# DB_Pheripherals-X01.net
KiCad netlist of a schematic drawn in Altium Designer
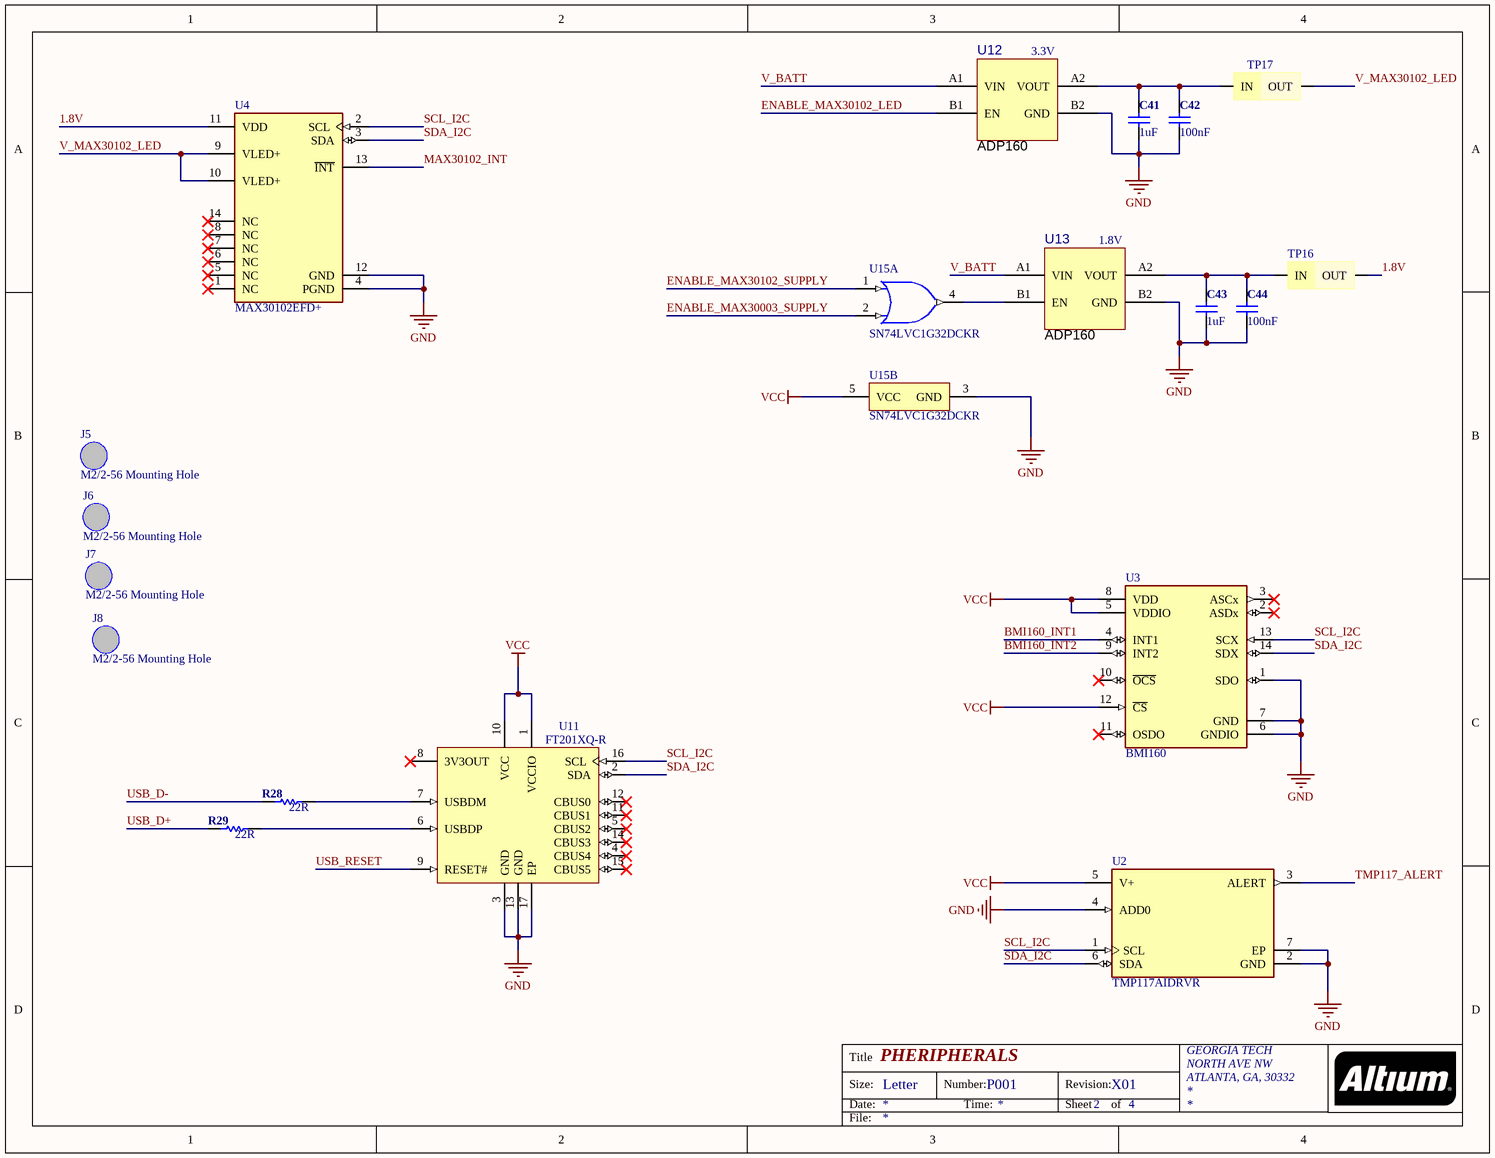
[diagram p0: DB_Pheripherals-X01.SchDoc]

(export (version "E")
  (design (tool "Eeschema 10.0.6"))
  (components
    (comp (ref "C41")
      (value "1uF")
      (footprint "C0402")
      (fields
        (field (name "MANUFACTURER") "Yageo")
        (field (name "MANUFACTURER PART NUMBER") "CC0402MRX5R5BB105")
        (field (name "TOLERANCE") "20%")
      )
      (libsource (lib "DB-X01") (part "C-0402(1005)"))
    )
    (comp (ref "C42")
      (value "100nF")
      (footprint "C0402")
      (fields
        (field (name "MANUFACTURER") "Taiyo Yuden")
        (field (name "MANUFACTURER PART NUMBER") "TMK105BJ104KV-F")
        (field (name "TOLERANCE") "10%")
      )
      (libsource (lib "DB-X01") (part "C-0402(1005)"))
    )
    (comp (ref "C43")
      (value "1uF")
      (footprint "C0402")
      (fields
        (field (name "MANUFACTURER") "Yageo")
        (field (name "MANUFACTURER PART NUMBER") "CC0402MRX5R5BB105")
        (field (name "TOLERANCE") "20%")
      )
      (libsource (lib "DB-X01") (part "C-0402(1005)"))
    )
    (comp (ref "C44")
      (value "100nF")
      (footprint "C0402")
      (fields
        (field (name "MANUFACTURER") "Taiyo Yuden")
        (field (name "MANUFACTURER PART NUMBER") "TMK105BJ104KV-F")
        (field (name "TOLERANCE") "10%")
      )
      (libsource (lib "DB-X01") (part "C-0402(1005)"))
    )
    (comp (ref "J5")
      (value "M2/2-56 Mounting Hole")
      (footprint "Mounting Hole")
      (libsource (lib "DB-X01") (part "M2/2-56 Mounting Hole"))
    )
    (comp (ref "J6")
      (value "M2/2-56 Mounting Hole")
      (footprint "Mounting Hole")
      (libsource (lib "DB-X01") (part "M2/2-56 Mounting Hole"))
    )
    (comp (ref "J7")
      (value "M2/2-56 Mounting Hole")
      (footprint "Mounting Hole")
      (libsource (lib "DB-X01") (part "M2/2-56 Mounting Hole"))
    )
    (comp (ref "J8")
      (value "M2/2-56 Mounting Hole")
      (footprint "Mounting Hole")
      (libsource (lib "DB-X01") (part "M2/2-56 Mounting Hole"))
    )
    (comp (ref "R28")
      (value "22R")
      (footprint "R0402")
      (fields
        (field (name "MANUFACTURER") "Yageo")
        (field (name "MANUFACTURER PART NUMBER") "RC0402JR-0722RL")
        (field (name "TOLERANCE") "5%")
      )
      (libsource (lib "DB-X01") (part "R-0402(1005)"))
    )
    (comp (ref "R29")
      (value "22R")
      (footprint "R0402")
      (fields
        (field (name "MANUFACTURER") "Yageo")
        (field (name "MANUFACTURER PART NUMBER") "RC0402JR-0722RL")
        (field (name "TOLERANCE") "5%")
      )
      (libsource (lib "DB-X01") (part "R-0402(1005)"))
    )
    (comp (ref "TP16")
      (value "JUMPER")
      (footprint "JUMPER")
      (description "SHUNT LP W/HANDLE 2 POS 30AU")
      (fields
        (field (name "MANUFACTURER") "TE Connectivity")
        (field (name "MANUFACTURER PART NUMBER") "8815452")
      )
      (libsource (lib "DB-X01") (part "JUMPER"))
    )
    (comp (ref "TP17")
      (value "JUMPER")
      (footprint "JUMPER")
      (description "SHUNT LP W/HANDLE 2 POS 30AU")
      (fields
        (field (name "MANUFACTURER") "TE Connectivity")
        (field (name "MANUFACTURER PART NUMBER") "8815452")
      )
      (libsource (lib "DB-X01") (part "JUMPER"))
    )
    (comp (ref "U2")
      (value "TMP117AIDRVR")
      (footprint "TMP117AIDRVR")
      (description "TEMPERATURE SENSOR")
      (fields
        (field (name "OCTOPART") "https://octopart.com/tmp117aidrvr-texas+instruments-95511044")
        (field (name "MANUFACTURER") "Texas Instruments")
      )
      (libsource (lib "DB-X01") (part "bceab6869a9cb85cf5675529ee35ce4"))
    )
    (comp (ref "U3")
      (value "BMI160")
      (footprint "FP-BMI160-MFG")
      (description "IMU ACCEL/GYRO I2C/SPI 14LGA")
      (fields (field (name "MANUFACTURER") "Bosch"))
      (libsource (lib "Altium Content Vault") (part "8c6a6e99292f3a8d44c06b20d07aef1"))
    )
    (comp (ref "U4")
      (value "MAX30102EFD+")
      (footprint "FP-F143A5-1-MFG")
      (description "IC SENSOR OXIMETER/HEARTRATE")
      (fields (field (name "MANUFACTURER") "Maxim"))
      (libsource (lib "Altium Content Vault") (part "5fad416c1761f996ad02d0b395f9532"))
    )
    (comp (ref "U11")
      (value "FT201XQ-R")
      (footprint "QFN-16_N")
      (fields (field (name "MANUFACTURER") "FTDI"))
      (libsource (lib "DB-X01") (part "COM-USB-FT201XQ-SQ17"))
    )
    (comp (ref "U12")
      (value "ADP160")
      (footprint "ADP160")
      (description "Fixed Positive LDO Regulator, 3.3V, 0.195V Dropout, CMOS, PBGA4")
      (fields
        (field (name "MANUFACTURER") "Analog Devices")
        (field (name "MANUFACTURER PART NUMBER") "ADP160ACBZ-3.3-R7")
        (field (name "OUTPUT VOLTAGE") "3.3V")
      )
      (libsource (lib "DB-X01") (part "ADP160-3_3V"))
    )
    (comp (ref "U13")
      (value "ADP160")
      (footprint "ADP160")
      (description "Fixed Positive LDO Regulator, 1.8V, 0.195V Dropout, CMOS, PBGA4")
      (fields
        (field (name "MANUFACTURER") "Analog Devices")
        (field (name "MANUFACTURER PART NUMBER") "ADP160ACBZ-1.8-R7")
        (field (name "OUTPUT VOLTAGE") "1.8V")
      )
      (libsource (lib "DB-X01") (part "ADP160-1_8V"))
    )
    (comp (ref "U15")
      (value "SN74LVC1G32DCKR")
      (footprint "DCK0005A_N")
      (description "Single 2-Input Positive-OR Gate, DCK0005A, LARGE T&R")
      (fields (field (name "MANUFACTURER") "Texas Instruments"))
      (libsource (lib "Altium Content Vault") (part "TI-SN74XXX1X32-5"))
    )
  )
  (nets
    (net (code "1") (name "/1.8V") (class "Default")
      (node (ref "TP16") (pin "2") (pinfunction "OUT_2") (pintype "passive"))
      (node (ref "U4") (pin "11") (pinfunction "VDD_11") (pintype "power_in"))
    )
    (net (code "2") (name "/BMI160_INT1") (class "Default")
      (node (ref "U3") (pin "4") (pinfunction "INT1_4") (pintype "bidirectional"))
    )
    (net (code "3") (name "/BMI160_INT2") (class "Default")
      (node (ref "U3") (pin "9") (pinfunction "INT2_9") (pintype "bidirectional"))
    )
    (net (code "4") (name "/ENABLE_MAX30003_SUPPLY") (class "Default")
      (node (ref "U15") (pin "2") (pinfunction "B_2") (pintype "input"))
    )
    (net (code "5") (name "/ENABLE_MAX30102_LED") (class "Default")
      (node (ref "U12") (pin "B1") (pinfunction "EN_B1") (pintype "passive"))
    )
    (net (code "6") (name "/ENABLE_MAX30102_SUPPLY") (class "Default")
      (node (ref "U15") (pin "1") (pinfunction "A_1") (pintype "input"))
    )
    (net (code "7") (name "/MAX30102_INT") (class "Default")
      (node (ref "U4") (pin "13") (pinfunction "~{INT}_13") (pintype "open_collector"))
    )
    (net (code "8") (name "/SCL_I2C") (class "Default")
      (node (ref "U11") (pin "16") (pinfunction "SCL_16") (pintype "input"))
      (node (ref "U2") (pin "1") (pinfunction "SCL_1") (pintype "input"))
      (node (ref "U3") (pin "13") (pinfunction "SCX_13") (pintype "input"))
      (node (ref "U4") (pin "2") (pinfunction "SCL_2") (pintype "input"))
    )
    (net (code "9") (name "/SDA_I2C") (class "Default")
      (node (ref "U11") (pin "2") (pinfunction "SDA_2") (pintype "bidirectional"))
      (node (ref "U2") (pin "6") (pinfunction "SDA_6") (pintype "bidirectional"))
      (node (ref "U3") (pin "14") (pinfunction "SDX_14") (pintype "bidirectional"))
      (node (ref "U4") (pin "3") (pinfunction "SDA_3") (pintype "bidirectional"))
    )
    (net (code "10") (name "/TMP117_ALERT") (class "Default")
      (node (ref "U2") (pin "3") (pinfunction "ALERT_3") (pintype "output"))
    )
    (net (code "11") (name "/USB_D+") (class "Default")
      (node (ref "R29") (pin "1") (pinfunction "1_1") (pintype "passive"))
    )
    (net (code "12") (name "/USB_D-") (class "Default")
      (node (ref "R28") (pin "1") (pinfunction "1_1") (pintype "passive"))
    )
    (net (code "13") (name "/USB_RESET") (class "Default")
      (node (ref "U11") (pin "9") (pinfunction "RESET#_9") (pintype "input"))
    )
    (net (code "14") (name "/V_BATT") (class "Default")
      (node (ref "U12") (pin "A1") (pinfunction "VIN_A1") (pintype "passive"))
      (node (ref "U13") (pin "A1") (pinfunction "VIN_A1") (pintype "passive"))
    )
    (net (code "15") (name "/V_MAX30102_LED") (class "Default")
      (node (ref "TP17") (pin "2") (pinfunction "OUT_2") (pintype "passive"))
      (node (ref "U4") (pin "10") (pinfunction "VLED+_10") (pintype "power_in"))
      (node (ref "U4") (pin "9") (pinfunction "VLED+_9") (pintype "power_in"))
    )
    (net (code "16") (name "GND") (class "Default")
      (node (ref "C41") (pin "2") (pinfunction "2_2") (pintype "passive"))
      (node (ref "C42") (pin "1") (pinfunction "1_1") (pintype "passive"))
      (node (ref "C43") (pin "2") (pinfunction "2_2") (pintype "passive"))
      (node (ref "C44") (pin "1") (pinfunction "1_1") (pintype "passive"))
      (node (ref "U11") (pin "13") (pinfunction "GND_13") (pintype "power_in"))
      (node (ref "U11") (pin "17") (pinfunction "EP_17") (pintype "power_in"))
      (node (ref "U11") (pin "3") (pinfunction "GND_3") (pintype "power_in"))
      (node (ref "U12") (pin "B2") (pinfunction "GND_B2") (pintype "passive"))
      (node (ref "U13") (pin "B2") (pinfunction "GND_B2") (pintype "passive"))
      (node (ref "U15") (pin "3") (pinfunction "GND_3") (pintype "power_in"))
      (node (ref "U2") (pin "2") (pinfunction "GND_2") (pintype "power_in"))
      (node (ref "U2") (pin "4") (pinfunction "ADD0_4") (pintype "input"))
      (node (ref "U2") (pin "7") (pinfunction "EP_7") (pintype "passive"))
      (node (ref "U3") (pin "1") (pinfunction "SDO_1") (pintype "bidirectional"))
      (node (ref "U3") (pin "6") (pinfunction "GNDIO_6") (pintype "power_in"))
      (node (ref "U3") (pin "7") (pinfunction "GND_7") (pintype "power_in"))
      (node (ref "U4") (pin "12") (pinfunction "GND_12") (pintype "power_in"))
      (node (ref "U4") (pin "4") (pinfunction "PGND_4") (pintype "power_in"))
    )
    (net (code "17") (name "Net-(TP16-IN)") (class "Default")
      (node (ref "C43") (pin "1") (pinfunction "1_1") (pintype "passive"))
      (node (ref "C44") (pin "2") (pinfunction "2_2") (pintype "passive"))
      (node (ref "TP16") (pin "1") (pinfunction "IN_1") (pintype "passive"))
      (node (ref "U13") (pin "A2") (pinfunction "VOUT_A2") (pintype "passive"))
    )
    (net (code "18") (name "Net-(TP17-IN)") (class "Default")
      (node (ref "C41") (pin "1") (pinfunction "1_1") (pintype "passive"))
      (node (ref "C42") (pin "2") (pinfunction "2_2") (pintype "passive"))
      (node (ref "TP17") (pin "1") (pinfunction "IN_1") (pintype "passive"))
      (node (ref "U12") (pin "A2") (pinfunction "VOUT_A2") (pintype "passive"))
    )
    (net (code "19") (name "Net-(U11-USBDM)") (class "Default")
      (node (ref "R28") (pin "2") (pinfunction "2_2") (pintype "passive"))
      (node (ref "U11") (pin "7") (pinfunction "USBDM_7") (pintype "input"))
    )
    (net (code "20") (name "Net-(U11-USBDP)") (class "Default")
      (node (ref "R29") (pin "2") (pinfunction "2_2") (pintype "passive"))
      (node (ref "U11") (pin "6") (pinfunction "USBDP_6") (pintype "input"))
    )
    (net (code "21") (name "Net-(U13-EN)") (class "Default")
      (node (ref "U13") (pin "B1") (pinfunction "EN_B1") (pintype "passive"))
      (node (ref "U15") (pin "4") (pinfunction "Y_4") (pintype "output"))
    )
    (net (code "22") (name "VCC") (class "Default")
      (node (ref "U11") (pin "1") (pinfunction "VCCIO_1") (pintype "power_in"))
      (node (ref "U11") (pin "10") (pinfunction "VCC_10") (pintype "power_in"))
      (node (ref "U15") (pin "5") (pinfunction "VCC_5") (pintype "power_in"))
      (node (ref "U2") (pin "5") (pinfunction "V+_5") (pintype "power_in"))
      (node (ref "U3") (pin "12") (pinfunction "~{CS}_12") (pintype "input"))
      (node (ref "U3") (pin "5") (pinfunction "VDDIO_5") (pintype "power_in"))
      (node (ref "U3") (pin "8") (pinfunction "VDD_8") (pintype "power_in"))
    )
    (net (code "23") (name "unconnected-(U3-ASCx-Pad3)") (class "Default")
      (node (ref "U3") (pin "3") (pinfunction "ASCx_3") (pintype "output+no_connect"))
    )
    (net (code "24") (name "unconnected-(U3-ASDx-Pad2)") (class "Default")
      (node (ref "U3") (pin "2") (pinfunction "ASDx_2") (pintype "bidirectional+no_connect"))
    )
    (net (code "25") (name "unconnected-(U3-OSDO-Pad11)") (class "Default")
      (node (ref "U3") (pin "11") (pinfunction "OSDO_11") (pintype "bidirectional+no_connect"))
    )
    (net (code "26") (name "unconnected-(U3-~{OCS}-Pad10)") (class "Default")
      (node (ref "U3") (pin "10") (pinfunction "~{OCS}_10") (pintype "bidirectional+no_connect"))
    )
    (net (code "27") (name "unconnected-(U4-NC-Pad1)") (class "Default")
      (node (ref "U4") (pin "1") (pinfunction "NC_1") (pintype "passive+no_connect"))
    )
    (net (code "28") (name "unconnected-(U4-NC-Pad5)") (class "Default")
      (node (ref "U4") (pin "5") (pinfunction "NC_5") (pintype "passive+no_connect"))
    )
    (net (code "29") (name "unconnected-(U4-NC-Pad6)") (class "Default")
      (node (ref "U4") (pin "6") (pinfunction "NC_6") (pintype "passive+no_connect"))
    )
    (net (code "30") (name "unconnected-(U4-NC-Pad7)") (class "Default")
      (node (ref "U4") (pin "7") (pinfunction "NC_7") (pintype "passive+no_connect"))
    )
    (net (code "31") (name "unconnected-(U4-NC-Pad8)") (class "Default")
      (node (ref "U4") (pin "8") (pinfunction "NC_8") (pintype "passive+no_connect"))
    )
    (net (code "32") (name "unconnected-(U4-NC-Pad14)") (class "Default")
      (node (ref "U4") (pin "14") (pinfunction "NC_14") (pintype "passive+no_connect"))
    )
    (net (code "33") (name "unconnected-(U11-3V3OUT-Pad8)") (class "Default")
      (node (ref "U11") (pin "8") (pinfunction "3V3OUT_8") (pintype "power_in+no_connect"))
    )
    (net (code "34") (name "unconnected-(U11-CBUS0-Pad12)") (class "Default")
      (node (ref "U11") (pin "12") (pinfunction "CBUS0_12") (pintype "bidirectional+no_connect"))
    )
    (net (code "35") (name "unconnected-(U11-CBUS1-Pad11)") (class "Default")
      (node (ref "U11") (pin "11") (pinfunction "CBUS1_11") (pintype "bidirectional+no_connect"))
    )
    (net (code "36") (name "unconnected-(U11-CBUS2-Pad5)") (class "Default")
      (node (ref "U11") (pin "5") (pinfunction "CBUS2_5") (pintype "bidirectional+no_connect"))
    )
    (net (code "37") (name "unconnected-(U11-CBUS3-Pad14)") (class "Default")
      (node (ref "U11") (pin "14") (pinfunction "CBUS3_14") (pintype "bidirectional+no_connect"))
    )
    (net (code "38") (name "unconnected-(U11-CBUS4-Pad4)") (class "Default")
      (node (ref "U11") (pin "4") (pinfunction "CBUS4_4") (pintype "bidirectional+no_connect"))
    )
    (net (code "39") (name "unconnected-(U11-CBUS5-Pad15)") (class "Default")
      (node (ref "U11") (pin "15") (pinfunction "CBUS5_15") (pintype "bidirectional+no_connect"))
    )
  )
)
